# battery_protection.net
KiCad netlist of a schematic drawn in Altium Designer
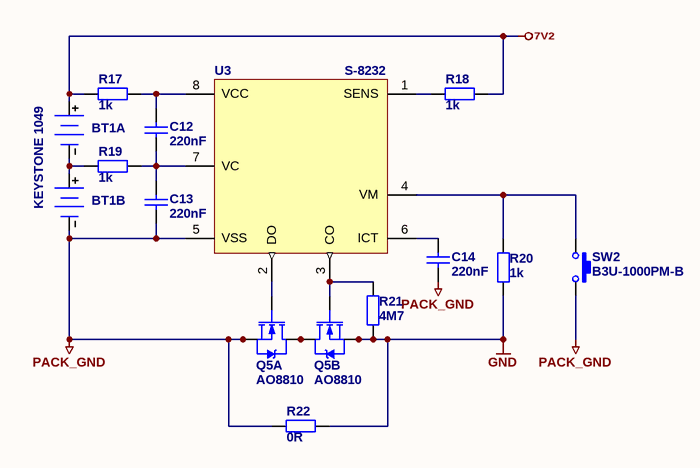
[diagram p0: battery_protection.SchDoc]

(export (version "E")
  (design (tool "Eeschema 10.0.6"))
  (components
    (comp (ref "BT1")
      (value "KEYSTONE 1049")
      (footprint "KEYSTONE_1049")
      (description "2x 18650 LiPo Acu in the KEYSTONE 1049 Holder")
      (libsource (lib "baterries_and_accus") (part "Keystone 1049"))
    )
    (comp (ref "C12")
      (value "220nF")
      (footprint "C0805")
      (description "Capacitor")
      (libsource (lib "capacitors") (part "Cap"))
    )
    (comp (ref "C13")
      (value "220nF")
      (footprint "C0805")
      (description "Capacitor")
      (libsource (lib "capacitors") (part "Cap"))
    )
    (comp (ref "C14")
      (value "220nF")
      (footprint "C0805")
      (description "Capacitor")
      (libsource (lib "capacitors") (part "Cap"))
    )
    (comp (ref "Q5")
      (value "AO8810")
      (footprint "TSSOP8")
      (description "Dual Common Drain N-Channel MOSFET: Vds=20V, Rdson<20mR@4,5V, Id=7A")
      (libsource (lib "transistors_mos") (part "AO8810"))
    )
    (comp (ref "R17")
      (value "1k")
      (footprint "R0805")
      (description "Resistor")
      (libsource (lib "") (part "Res_1"))
    )
    (comp (ref "R18")
      (value "1k")
      (footprint "R0805")
      (description "Resistor")
      (libsource (lib "") (part "Res_1"))
    )
    (comp (ref "R19")
      (value "1k")
      (footprint "R0805")
      (description "Resistor")
      (libsource (lib "") (part "Res_1"))
    )
    (comp (ref "R20")
      (value "1k")
      (footprint "R0805")
      (description "Resistor")
      (libsource (lib "") (part "Res_2"))
    )
    (comp (ref "R21")
      (value "4M7")
      (footprint "R0805")
      (description "Resistor")
      (libsource (lib "") (part "Res_2"))
    )
    (comp (ref "R22")
      (value "0R")
      (footprint "R0805")
      (description "Resistor")
      (libsource (lib "resistors") (part "Res"))
    )
    (comp (ref "SW2")
      (value "B3U-1000PM-B")
      (footprint "B3U-1000PM-B")
      (description "OMRON Ultra-small Tactile Switch - 12V/50mA")
      (libsource (lib "microswitches") (part "B3U-1000PM-B"))
    )
    (comp (ref "U3")
      (value "S-8232")
      (footprint "TSSOP8")
      (description "Battery Protection IC For 2-Serial-Cell Pack")
      (libsource (lib "protection_circuits") (part "S-8232"))
    )
  )
  (nets
    (net (code "1") (name "7V2") (class "Default")
      (node (ref "BT1") (pin "1") (pinfunction "+_1") (pintype "passive"))
      (node (ref "R17") (pin "1") (pinfunction "1_1") (pintype "passive"))
      (node (ref "R18") (pin "2") (pinfunction "2_2") (pintype "passive"))
    )
    (net (code "2") (name "GND") (class "Default")
      (node (ref "Q5") (pin "6") (pinfunction "S2_6") (pintype "passive"))
      (node (ref "Q5") (pin "7") (pinfunction "S2_7") (pintype "passive"))
      (node (ref "R20") (pin "2") (pinfunction "2_2") (pintype "passive"))
      (node (ref "R21") (pin "2") (pinfunction "2_2") (pintype "passive"))
      (node (ref "R22") (pin "1") (pinfunction "1_1") (pintype "passive"))
    )
    (net (code "3") (name "Net-(BT1A--)") (class "Default")
      (node (ref "BT1") (pin "2") (pinfunction "-_2") (pintype "passive"))
      (node (ref "BT1") (pin "4") (pinfunction "+_4") (pintype "passive"))
      (node (ref "R19") (pin "1") (pinfunction "1_1") (pintype "passive"))
    )
    (net (code "4") (name "Net-(Q5A-D1{slash}D2)") (class "Default")
      (node (ref "Q5") (pin "1") (pinfunction "D1/D2_1") (pintype "passive"))
      (node (ref "Q5") (pin "8") (pinfunction "D1/D3_8") (pintype "passive"))
    )
    (net (code "5") (name "Net-(Q5A-G1)") (class "Default")
      (node (ref "Q5") (pin "4") (pinfunction "G1_4") (pintype "passive"))
      (node (ref "U3") (pin "2") (pinfunction "DO_2") (pintype "output"))
    )
    (net (code "6") (name "Net-(Q5B-G2)") (class "Default")
      (node (ref "Q5") (pin "5") (pinfunction "G2_5") (pintype "passive"))
      (node (ref "R21") (pin "1") (pinfunction "1_1") (pintype "passive"))
      (node (ref "U3") (pin "3") (pinfunction "CO_3") (pintype "output"))
    )
    (net (code "7") (name "Net-(U3-ICT)") (class "Default")
      (node (ref "C14") (pin "2") (pinfunction "2_2") (pintype "passive"))
      (node (ref "U3") (pin "6") (pinfunction "ICT_6") (pintype "passive"))
    )
    (net (code "8") (name "Net-(U3-SENS)") (class "Default")
      (node (ref "R18") (pin "1") (pinfunction "1_1") (pintype "passive"))
      (node (ref "U3") (pin "1") (pinfunction "SENS_1") (pintype "passive"))
    )
    (net (code "9") (name "Net-(U3-VC)") (class "Default")
      (node (ref "C12") (pin "1") (pinfunction "1_1") (pintype "passive"))
      (node (ref "C13") (pin "2") (pinfunction "2_2") (pintype "passive"))
      (node (ref "R19") (pin "2") (pinfunction "2_2") (pintype "passive"))
      (node (ref "U3") (pin "7") (pinfunction "VC_7") (pintype "passive"))
    )
    (net (code "10") (name "Net-(U3-VCC)") (class "Default")
      (node (ref "C12") (pin "2") (pinfunction "2_2") (pintype "passive"))
      (node (ref "R17") (pin "2") (pinfunction "2_2") (pintype "passive"))
      (node (ref "U3") (pin "8") (pinfunction "VCC_8") (pintype "passive"))
    )
    (net (code "11") (name "Net-(U3-VM)") (class "Default")
      (node (ref "R20") (pin "1") (pinfunction "1_1") (pintype "passive"))
      (node (ref "SW2") (pin "1") (pinfunction "1_1") (pintype "passive"))
      (node (ref "U3") (pin "4") (pinfunction "VM_4") (pintype "passive"))
    )
    (net (code "12") (name "PACK_GND") (class "Default")
      (node (ref "BT1") (pin "3") (pinfunction "-_3") (pintype "passive"))
      (node (ref "C13") (pin "1") (pinfunction "1_1") (pintype "passive"))
      (node (ref "C14") (pin "1") (pinfunction "1_1") (pintype "passive"))
      (node (ref "Q5") (pin "2") (pinfunction "S1_2") (pintype "passive"))
      (node (ref "Q5") (pin "3") (pinfunction "S1_3") (pintype "passive"))
      (node (ref "R22") (pin "2") (pinfunction "2_2") (pintype "passive"))
      (node (ref "SW2") (pin "2") (pinfunction "2_2") (pintype "passive"))
      (node (ref "U3") (pin "5") (pinfunction "VSS_5") (pintype "passive"))
    )
  )
)
